# PENAMPUNG_URIN.net
KiCad netlist of a schematic drawn in EAGLE
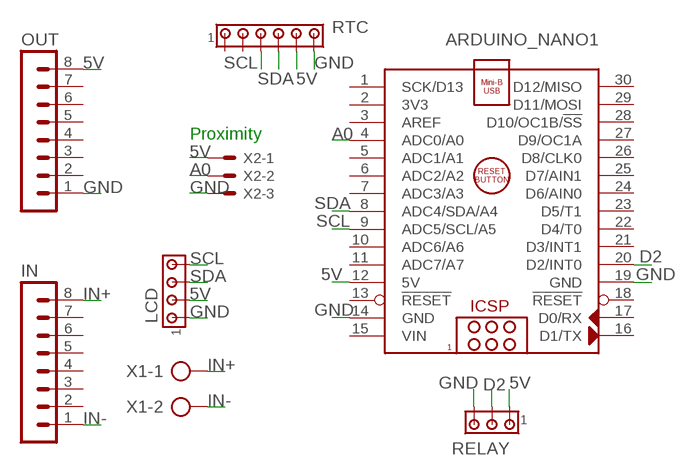
[diagram p0: schematic, sheet 1]

(export (version "E")
  (design (tool "Eeschema 10.0.6"))
  (components
    (comp (ref "ARDUINO_NANO1")
      (value "ARDUINO_NANO")
      (footprint "eagle-import:ARDUINO_NANO")
      (libsource (lib "eagle-import") (part "ARDUINO_NANO"))
    )
    (comp (ref "IN")
      (value "MA08-1")
      (footprint "eagle-import:MA08-1")
      (libsource (lib "eagle-import") (part "MA08-1"))
    )
    (comp (ref "LCD")
      (value "MTA04-100")
      (footprint "eagle-import:10X04MTA")
      (libsource (lib "eagle-import") (part "MTA04-100"))
    )
    (comp (ref "OUT")
      (value "MA08-1")
      (footprint "eagle-import:MA08-1")
      (libsource (lib "eagle-import") (part "MA08-1"))
    )
    (comp (ref "RELAY")
      (value "MTA03-100")
      (footprint "eagle-import:10X03MTA")
      (libsource (lib "eagle-import") (part "MTA03-100"))
    )
    (comp (ref "RTC")
      (value "MTA06-100")
      (footprint "eagle-import:10X06MTA")
      (libsource (lib "eagle-import") (part "MTA06-100"))
    )
    (comp (ref "X1")
      (value "AK500/2-H")
      (footprint "eagle-import:AK500_2-H")
      (libsource (lib "eagle-import") (part "AK500/2-H"))
    )
    (comp (ref "X2")
      (value "KK-156-3")
      (footprint "eagle-import:KK-156-3")
      (fields (field (name "MF") "MOLEX"))
      (libsource (lib "eagle-import") (part "KK-156-3"))
    )
  )
  (nets
    (net (code "1") (name "/5V") (class "Default")
      (node (ref "ARDUINO_NANO1") (pin "12") (pinfunction "5V_12") (pintype "power_in"))
      (node (ref "LCD") (pin "2") (pinfunction "2_2") (pintype "passive"))
      (node (ref "OUT") (pin "8") (pinfunction "8_8") (pintype "passive"))
      (node (ref "RELAY") (pin "1") (pinfunction "1_1") (pintype "passive"))
      (node (ref "RTC") (pin "5") (pinfunction "5_5") (pintype "passive"))
      (node (ref "X2") (pin "1") (pinfunction "S_1") (pintype "passive"))
    )
    (net (code "2") (name "/A0") (class "Default")
      (node (ref "ARDUINO_NANO1") (pin "4") (pinfunction "ADC0/A0_4") (pintype "bidirectional"))
      (node (ref "X2") (pin "2") (pinfunction "S_2") (pintype "passive"))
    )
    (net (code "3") (name "/D2") (class "Default")
      (node (ref "ARDUINO_NANO1") (pin "20") (pinfunction "D2/INT0_20") (pintype "bidirectional"))
      (node (ref "RELAY") (pin "2") (pinfunction "2_2") (pintype "passive"))
    )
    (net (code "4") (name "/GND") (class "Default")
      (node (ref "ARDUINO_NANO1") (pin "14") (pinfunction "GND_14") (pintype "power_in"))
      (node (ref "ARDUINO_NANO1") (pin "19") (pinfunction "GND_19") (pintype "power_in"))
      (node (ref "LCD") (pin "1") (pinfunction "1_1") (pintype "passive"))
      (node (ref "OUT") (pin "1") (pinfunction "1_1") (pintype "passive"))
      (node (ref "RELAY") (pin "3") (pinfunction "3_3") (pintype "passive"))
      (node (ref "RTC") (pin "6") (pinfunction "6_6") (pintype "passive"))
      (node (ref "X2") (pin "3") (pinfunction "S_3") (pintype "passive"))
    )
    (net (code "5") (name "/IN+") (class "Default")
      (node (ref "IN") (pin "8") (pinfunction "8_8") (pintype "passive"))
      (node (ref "X1") (pin "1") (pinfunction "KL_1") (pintype "passive"))
    )
    (net (code "6") (name "/IN-") (class "Default")
      (node (ref "IN") (pin "1") (pinfunction "1_1") (pintype "passive"))
      (node (ref "X1") (pin "2") (pinfunction "KL_2") (pintype "passive"))
    )
    (net (code "7") (name "/SCL") (class "Default")
      (node (ref "ARDUINO_NANO1") (pin "9") (pinfunction "ADC5/SCL/A5_9") (pintype "bidirectional"))
      (node (ref "LCD") (pin "4") (pinfunction "4_4") (pintype "passive"))
      (node (ref "RTC") (pin "3") (pinfunction "3_3") (pintype "passive"))
    )
    (net (code "8") (name "/SDA") (class "Default")
      (node (ref "ARDUINO_NANO1") (pin "8") (pinfunction "ADC4/SDA/A4_8") (pintype "bidirectional"))
      (node (ref "LCD") (pin "3") (pinfunction "3_3") (pintype "passive"))
      (node (ref "RTC") (pin "4") (pinfunction "4_4") (pintype "passive"))
    )
    (net (code "9") (name "/VIN") (class "Default")
      (node (ref "ARDUINO_NANO1") (pin "15") (pinfunction "VIN_15") (pintype "power_in"))
    )
    (net (code "10") (name "unconnected-(ARDUINO_NANO1-3V3-Pad2)") (class "Default")
      (node (ref "ARDUINO_NANO1") (pin "2") (pinfunction "3V3_2") (pintype "output"))
    )
    (net (code "11") (name "unconnected-(ARDUINO_NANO1-ADC1{slash}A1-Pad5)") (class "Default")
      (node (ref "ARDUINO_NANO1") (pin "5") (pinfunction "ADC1/A1_5") (pintype "bidirectional"))
    )
    (net (code "12") (name "unconnected-(ARDUINO_NANO1-ADC2{slash}A2-Pad6)") (class "Default")
      (node (ref "ARDUINO_NANO1") (pin "6") (pinfunction "ADC2/A2_6") (pintype "bidirectional"))
    )
    (net (code "13") (name "unconnected-(ARDUINO_NANO1-ADC3{slash}A3-Pad7)") (class "Default")
      (node (ref "ARDUINO_NANO1") (pin "7") (pinfunction "ADC3/A3_7") (pintype "bidirectional"))
    )
    (net (code "14") (name "unconnected-(ARDUINO_NANO1-ADC6{slash}A6-Pad10)") (class "Default")
      (node (ref "ARDUINO_NANO1") (pin "10") (pinfunction "ADC6/A6_10") (pintype "bidirectional"))
    )
    (net (code "15") (name "unconnected-(ARDUINO_NANO1-ADC7{slash}A7-Pad11)") (class "Default")
      (node (ref "ARDUINO_NANO1") (pin "11") (pinfunction "ADC7/A7_11") (pintype "bidirectional"))
    )
    (net (code "16") (name "unconnected-(ARDUINO_NANO1-AREF-Pad3)") (class "Default")
      (node (ref "ARDUINO_NANO1") (pin "3") (pinfunction "AREF_3") (pintype "input"))
    )
    (net (code "17") (name "unconnected-(ARDUINO_NANO1-D0{slash}RX-Pad17)") (class "Default")
      (node (ref "ARDUINO_NANO1") (pin "17") (pinfunction "D0/RX_17") (pintype "bidirectional"))
    )
    (net (code "18") (name "unconnected-(ARDUINO_NANO1-D1{slash}TX-Pad16)") (class "Default")
      (node (ref "ARDUINO_NANO1") (pin "16") (pinfunction "D1/TX_16") (pintype "bidirectional"))
    )
    (net (code "19") (name "unconnected-(ARDUINO_NANO1-D3{slash}INT1-Pad21)") (class "Default")
      (node (ref "ARDUINO_NANO1") (pin "21") (pinfunction "D3/INT1_21") (pintype "bidirectional"))
    )
    (net (code "20") (name "unconnected-(ARDUINO_NANO1-D4{slash}T0-Pad22)") (class "Default")
      (node (ref "ARDUINO_NANO1") (pin "22") (pinfunction "D4/T0_22") (pintype "bidirectional"))
    )
    (net (code "21") (name "unconnected-(ARDUINO_NANO1-D5{slash}T1-Pad23)") (class "Default")
      (node (ref "ARDUINO_NANO1") (pin "23") (pinfunction "D5/T1_23") (pintype "bidirectional"))
    )
    (net (code "22") (name "unconnected-(ARDUINO_NANO1-D6{slash}AIN0-Pad24)") (class "Default")
      (node (ref "ARDUINO_NANO1") (pin "24") (pinfunction "D6/AIN0_24") (pintype "bidirectional"))
    )
    (net (code "23") (name "unconnected-(ARDUINO_NANO1-D7{slash}AIN1-Pad25)") (class "Default")
      (node (ref "ARDUINO_NANO1") (pin "25") (pinfunction "D7/AIN1_25") (pintype "bidirectional"))
    )
    (net (code "24") (name "unconnected-(ARDUINO_NANO1-D8{slash}CLK0-Pad26)") (class "Default")
      (node (ref "ARDUINO_NANO1") (pin "26") (pinfunction "D8/CLK0_26") (pintype "bidirectional"))
    )
    (net (code "25") (name "unconnected-(ARDUINO_NANO1-D9{slash}OC1A-Pad27)") (class "Default")
      (node (ref "ARDUINO_NANO1") (pin "27") (pinfunction "D9/OC1A_27") (pintype "bidirectional"))
    )
    (net (code "26") (name "unconnected-(ARDUINO_NANO1-D10{slash}OC1B{slash}~{SS}-Pad28)") (class "Default")
      (node (ref "ARDUINO_NANO1") (pin "28") (pinfunction "D10/OC1B/~{SS}_28") (pintype "bidirectional"))
    )
    (net (code "27") (name "unconnected-(ARDUINO_NANO1-D11{slash}MOSI-Pad29)") (class "Default")
      (node (ref "ARDUINO_NANO1") (pin "29") (pinfunction "D11/MOSI_29") (pintype "bidirectional"))
    )
    (net (code "28") (name "unconnected-(ARDUINO_NANO1-D12{slash}MISO-Pad30)") (class "Default")
      (node (ref "ARDUINO_NANO1") (pin "30") (pinfunction "D12/MISO_30") (pintype "bidirectional"))
    )
    (net (code "29") (name "unconnected-(ARDUINO_NANO1-SCK{slash}D13-Pad1)") (class "Default")
      (node (ref "ARDUINO_NANO1") (pin "1") (pinfunction "SCK/D13_1") (pintype "bidirectional"))
    )
    (net (code "30") (name "unconnected-(ARDUINO_NANO1-~{RESET}-Pad13)") (class "Default")
      (node (ref "ARDUINO_NANO1") (pin "13") (pinfunction "~{RESET}_13") (pintype "input"))
    )
    (net (code "31") (name "unconnected-(ARDUINO_NANO1-~{RESET}-Pad18)") (class "Default")
      (node (ref "ARDUINO_NANO1") (pin "18") (pinfunction "~{RESET}_18") (pintype "input"))
    )
    (net (code "32") (name "unconnected-(IN-Pad2)") (class "Default")
      (node (ref "IN") (pin "2") (pinfunction "2_2") (pintype "passive"))
    )
    (net (code "33") (name "unconnected-(IN-Pad3)") (class "Default")
      (node (ref "IN") (pin "3") (pinfunction "3_3") (pintype "passive"))
    )
    (net (code "34") (name "unconnected-(IN-Pad4)") (class "Default")
      (node (ref "IN") (pin "4") (pinfunction "4_4") (pintype "passive"))
    )
    (net (code "35") (name "unconnected-(IN-Pad5)") (class "Default")
      (node (ref "IN") (pin "5") (pinfunction "5_5") (pintype "passive"))
    )
    (net (code "36") (name "unconnected-(IN-Pad6)") (class "Default")
      (node (ref "IN") (pin "6") (pinfunction "6_6") (pintype "passive"))
    )
    (net (code "37") (name "unconnected-(IN-Pad7)") (class "Default")
      (node (ref "IN") (pin "7") (pinfunction "7_7") (pintype "passive"))
    )
    (net (code "38") (name "unconnected-(OUT-Pad2)") (class "Default")
      (node (ref "OUT") (pin "2") (pinfunction "2_2") (pintype "passive"))
    )
    (net (code "39") (name "unconnected-(OUT-Pad3)") (class "Default")
      (node (ref "OUT") (pin "3") (pinfunction "3_3") (pintype "passive"))
    )
    (net (code "40") (name "unconnected-(OUT-Pad4)") (class "Default")
      (node (ref "OUT") (pin "4") (pinfunction "4_4") (pintype "passive"))
    )
    (net (code "41") (name "unconnected-(OUT-Pad5)") (class "Default")
      (node (ref "OUT") (pin "5") (pinfunction "5_5") (pintype "passive"))
    )
    (net (code "42") (name "unconnected-(OUT-Pad6)") (class "Default")
      (node (ref "OUT") (pin "6") (pinfunction "6_6") (pintype "passive"))
    )
    (net (code "43") (name "unconnected-(OUT-Pad7)") (class "Default")
      (node (ref "OUT") (pin "7") (pinfunction "7_7") (pintype "passive"))
    )
    (net (code "44") (name "unconnected-(RTC-Pad1)") (class "Default")
      (node (ref "RTC") (pin "1") (pinfunction "1_1") (pintype "passive"))
    )
    (net (code "45") (name "unconnected-(RTC-Pad2)") (class "Default")
      (node (ref "RTC") (pin "2") (pinfunction "2_2") (pintype "passive"))
    )
  )
)
